# Sheet1.net
KiCad netlist of a schematic drawn in Altium Designer
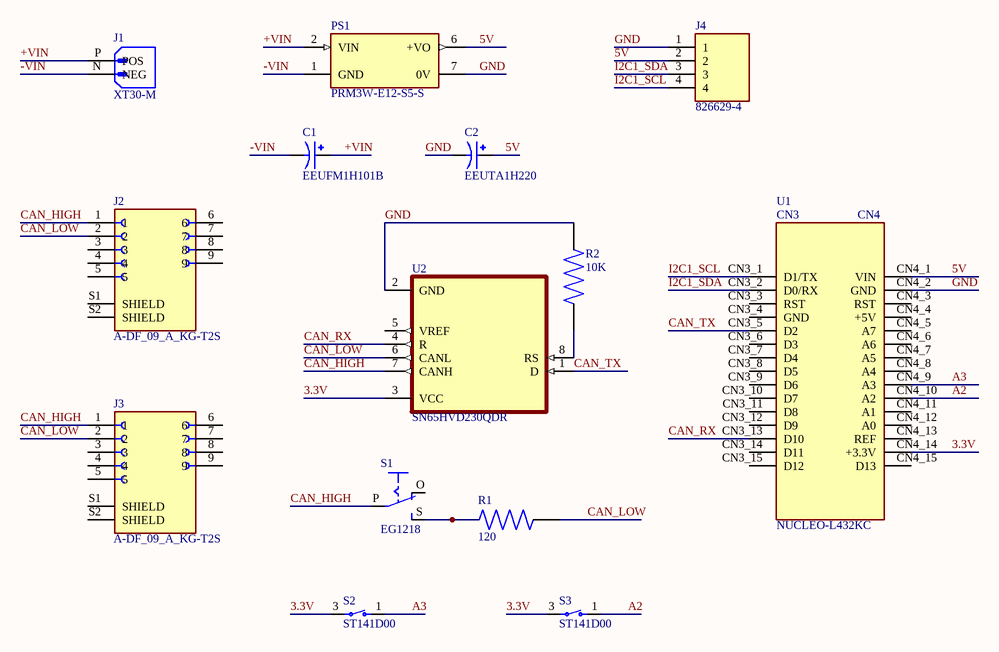
[diagram p0: Sheet1.SchDoc]

(export (version "E")
  (design (tool "Eeschema 10.0.6"))
  (components
    (comp (ref "C1")
      (value "EEUFM1H101B")
      (footprint "CAPPRD500W60D800H1150")
      (description "Cap Aluminum Lytic 100uF 50V 20% (8 X 11.5mm) Radial 5mm 870mA 3000h 105C Ammo Pack")
      (fields (field (name "MF") "Panasonic"))
      (libsource (lib "EEUFM1H101B") (part "EEUFM1H101B"))
    )
    (comp (ref "C2")
      (value "EEUTA1H220")
      (footprint "CAPPRD350W60D800H1150")
      (description "22F 50V Aluminum Electrolytic Capacitors Radial, Can 2000 Hrs @ 125C")
      (fields (field (name "MP") "EEU-TA1H220") (field (name "MF") "Panasonic"))
      (libsource (lib "EEUTA1H220") (part "EEUTA1H220"))
    )
    (comp (ref "J1")
      (value "XT30-M")
      (footprint "AMASS_XT60-M")
      (description "Plug; DC supply; XT60; male; PIN: 2; for cable; soldered; 30A; 500V")
      (fields (field (name "MP") "XT60-M") (field (name "MF") "AMASS"))
      (libsource (lib "XT30-M") (part "XT30-M"))
    )
    (comp (ref "J2")
      (value "A-DF_09_A_KG-T2S")
      (footprint "ASSMANN_A-DF_09_A_KG-T2S")
      (description "9 Position D-Sub Receptacle, Female Sockets Connector")
      (fields (field (name "MF") "Assmann WSW") (field (name "MP") "A-DF 09 A/KG-T2S"))
      (libsource (lib "A-DF_09_A_KG-T2S") (part "A-DF_09_A_KG-T2S"))
    )
    (comp (ref "J3")
      (value "A-DF_09_A_KG-T2S")
      (footprint "ASSMANN_A-DF_09_A_KG-T2S")
      (description "9 Position D-Sub Receptacle, Female Sockets Connector")
      (fields (field (name "MF") "Assmann WSW") (field (name "MP") "A-DF 09 A/KG-T2S"))
      (libsource (lib "A-DF_09_A_KG-T2S") (part "A-DF_09_A_KG-T2S"))
    )
    (comp (ref "J4")
      (value "826629-4")
      (footprint "TE_826629-4")
      (description "Conn Unshrouded Header HDR 4 POS 2.54mm Solder ST Thru-Hole Automotive Carton")
      (fields (field (name "MF") "TE Connectivity"))
      (libsource (lib "826629-4") (part "826629-4"))
    )
    (comp (ref "PS1")
      (value "PRM3W-E12-S5-S")
      (footprint "CONV_PRM3W-E12-S5-S")
      (fields (field (name "MF") "{'manufacturer': u'CUI'}"))
      (libsource (lib "PRM3W-E12-S5-S") (part "PRM3W-E12-S5-S"))
    )
    (comp (ref "R1")
      (value "120")
      (footprint "RESC3216X65N")
      (fields (field (name "MP") "KTR18EZPF9530"))
      (libsource (lib "KTR18EZPF9530") (part "KTR18EZPF9530"))
    )
    (comp (ref "R2")
      (value "10K")
      (footprint "RESC3216X65N")
      (fields (field (name "MP") "KTR18EZPF9530"))
      (libsource (lib "KTR18EZPF9530") (part "KTR18EZPF9530"))
    )
    (comp (ref "S1") (value "EG1218") (footprint "EG1218:EG1218") (libsource (lib "EG1218") (part "EG1218")))
    (comp (ref "S2")
      (value "ST141D00")
      (footprint "SW_ST141D00")
      (description "Toggle Switch SPST Panel Mount")
      (fields (field (name "MF") "E-Switch"))
      (libsource (lib "ST141D00") (part "ST141D00"))
    )
    (comp (ref "S3")
      (value "ST141D00")
      (footprint "SW_ST141D00")
      (description "Toggle Switch SPST Panel Mount")
      (fields (field (name "MF") "E-Switch"))
      (libsource (lib "ST141D00") (part "ST141D00"))
    )
    (comp (ref "U1")
      (value "NUCLEO-L432KC")
      (footprint "MODULE_NUCLEO-L432KC")
      (description "STM32 Nucleo-32 development board with STM32L432KC MCU, supports Arduino connectivity")
      (libsource (lib "NUCLEO-L432KC") (part "NUCLEO-L432KC"))
    )
    (comp (ref "U2")
      (value "SN65HVD230QDR")
      (footprint "SOIC127P599X175-8N")
      (description "3.3-V CAN Transceiver with Standby Mode 8-SOIC -40 to 125")
      (fields (field (name "MF") "Texas Instruments"))
      (libsource (lib "SN65HVD230QDR") (part "SN65HVD230QDR"))
    )
  )
  (nets
    (net (code "1") (name "/+VIN") (class "Default")
      (node (ref "C1") (pin "P") (pinfunction "P_P") (pintype "passive"))
      (node (ref "J1") (pin "P") (pinfunction "POS_P") (pintype "passive"))
      (node (ref "PS1") (pin "2") (pinfunction "VIN_2") (pintype "input"))
    )
    (net (code "2") (name "/-VIN") (class "Default")
      (node (ref "C1") (pin "N") (pinfunction "N_N") (pintype "passive"))
      (node (ref "J1") (pin "N") (pinfunction "NEG_N") (pintype "passive"))
      (node (ref "PS1") (pin "1") (pinfunction "GND_1") (pintype "power_in"))
    )
    (net (code "3") (name "/3.3V") (class "Default")
      (node (ref "S2") (pin "3") (pinfunction "3_3") (pintype "passive"))
      (node (ref "S3") (pin "3") (pinfunction "3_3") (pintype "passive"))
      (node (ref "U1") (pin "CN4_14") (pinfunction "+3.3V_CN4_14") (pintype "power_in"))
      (node (ref "U2") (pin "3") (pinfunction "VCC_3") (pintype "power_in"))
    )
    (net (code "4") (name "/5V") (class "Default")
      (node (ref "C2") (pin "P") (pinfunction "P_P") (pintype "passive"))
      (node (ref "J4") (pin "2") (pinfunction "2_2") (pintype "passive"))
      (node (ref "PS1") (pin "6") (pinfunction "+VO_6") (pintype "output"))
      (node (ref "U1") (pin "CN4_1") (pinfunction "VIN_CN4_1") (pintype "power_in"))
    )
    (net (code "5") (name "/A2") (class "Default")
      (node (ref "S3") (pin "1") (pinfunction "1_1") (pintype "passive"))
      (node (ref "U1") (pin "CN4_10") (pinfunction "A2_CN4_10") (pintype "passive"))
    )
    (net (code "6") (name "/A3") (class "Default")
      (node (ref "S2") (pin "1") (pinfunction "1_1") (pintype "passive"))
      (node (ref "U1") (pin "CN4_9") (pinfunction "A3_CN4_9") (pintype "passive"))
    )
    (net (code "7") (name "/CAN_HIGH") (class "Default")
      (node (ref "J2") (pin "1") (pinfunction "1_1") (pintype "passive"))
      (node (ref "J3") (pin "1") (pinfunction "1_1") (pintype "passive"))
      (node (ref "S1") (pin "P") (pinfunction "P_P") (pintype "passive"))
      (node (ref "U2") (pin "7") (pinfunction "CANH_7") (pintype "output"))
    )
    (net (code "8") (name "/CAN_LOW") (class "Default")
      (node (ref "J2") (pin "2") (pinfunction "2_2") (pintype "passive"))
      (node (ref "J3") (pin "2") (pinfunction "2_2") (pintype "passive"))
      (node (ref "R1") (pin "2") (pinfunction "2_2") (pintype "passive"))
      (node (ref "U2") (pin "6") (pinfunction "CANL_6") (pintype "output"))
    )
    (net (code "9") (name "/CAN_RX") (class "Default")
      (node (ref "U1") (pin "CN3_13") (pinfunction "D10_CN3_13") (pintype "passive"))
      (node (ref "U2") (pin "4") (pinfunction "R_4") (pintype "output"))
    )
    (net (code "10") (name "/CAN_TX") (class "Default")
      (node (ref "U1") (pin "CN3_5") (pinfunction "D2_CN3_5") (pintype "power_in"))
      (node (ref "U2") (pin "1") (pinfunction "D_1") (pintype "input"))
    )
    (net (code "11") (name "/GND") (class "Default")
      (node (ref "C2") (pin "N") (pinfunction "N_N") (pintype "passive"))
      (node (ref "J4") (pin "1") (pinfunction "1_1") (pintype "passive"))
      (node (ref "PS1") (pin "7") (pinfunction "0V_7") (pintype "passive"))
      (node (ref "R2") (pin "2") (pinfunction "2_2") (pintype "passive"))
      (node (ref "U1") (pin "CN4_2") (pinfunction "GND_CN4_2") (pintype "power_in"))
      (node (ref "U2") (pin "2") (pinfunction "GND_2") (pintype "power_in"))
    )
    (net (code "12") (name "/I2C1_SCL") (class "Default")
      (node (ref "J4") (pin "4") (pinfunction "4_4") (pintype "passive"))
      (node (ref "U1") (pin "CN3_1") (pinfunction "D1/TX_CN3_1") (pintype "power_in"))
    )
    (net (code "13") (name "/I2C1_SDA") (class "Default")
      (node (ref "J4") (pin "3") (pinfunction "3_3") (pintype "passive"))
      (node (ref "U1") (pin "CN3_2") (pinfunction "D0/RX_CN3_2") (pintype "power_in"))
    )
    (net (code "14") (name "Net-(R1-Pad1)") (class "Default")
      (node (ref "R1") (pin "1") (pinfunction "1_1") (pintype "passive"))
      (node (ref "S1") (pin "S") (pinfunction "S_S") (pintype "passive"))
    )
    (net (code "15") (name "Net-(U2-RS)") (class "Default")
      (node (ref "R2") (pin "1") (pinfunction "1_1") (pintype "passive"))
      (node (ref "U2") (pin "8") (pinfunction "RS_8") (pintype "input"))
    )
    (net (code "16") (name "unconnected-(J2-Pad3)") (class "Default")
      (node (ref "J2") (pin "3") (pinfunction "3_3") (pintype "passive"))
    )
    (net (code "17") (name "unconnected-(J2-Pad4)") (class "Default")
      (node (ref "J2") (pin "4") (pinfunction "4_4") (pintype "passive"))
    )
    (net (code "18") (name "unconnected-(J2-Pad5)") (class "Default")
      (node (ref "J2") (pin "5") (pinfunction "5_5") (pintype "passive"))
    )
    (net (code "19") (name "unconnected-(J2-Pad6)") (class "Default")
      (node (ref "J2") (pin "6") (pinfunction "6_6") (pintype "passive"))
    )
    (net (code "20") (name "unconnected-(J2-Pad7)") (class "Default")
      (node (ref "J2") (pin "7") (pinfunction "7_7") (pintype "passive"))
    )
    (net (code "21") (name "unconnected-(J2-Pad8)") (class "Default")
      (node (ref "J2") (pin "8") (pinfunction "8_8") (pintype "passive"))
    )
    (net (code "22") (name "unconnected-(J2-Pad9)") (class "Default")
      (node (ref "J2") (pin "9") (pinfunction "9_9") (pintype "passive"))
    )
    (net (code "23") (name "unconnected-(J2-SHIELD-PadS1)") (class "Default")
      (node (ref "J2") (pin "S1") (pinfunction "SHIELD_S1") (pintype "passive"))
    )
    (net (code "24") (name "unconnected-(J2-SHIELD-PadS2)") (class "Default")
      (node (ref "J2") (pin "S2") (pinfunction "SHIELD_S2") (pintype "passive"))
    )
    (net (code "25") (name "unconnected-(J3-Pad3)") (class "Default")
      (node (ref "J3") (pin "3") (pinfunction "3_3") (pintype "passive"))
    )
    (net (code "26") (name "unconnected-(J3-Pad4)") (class "Default")
      (node (ref "J3") (pin "4") (pinfunction "4_4") (pintype "passive"))
    )
    (net (code "27") (name "unconnected-(J3-Pad5)") (class "Default")
      (node (ref "J3") (pin "5") (pinfunction "5_5") (pintype "passive"))
    )
    (net (code "28") (name "unconnected-(J3-Pad6)") (class "Default")
      (node (ref "J3") (pin "6") (pinfunction "6_6") (pintype "passive"))
    )
    (net (code "29") (name "unconnected-(J3-Pad7)") (class "Default")
      (node (ref "J3") (pin "7") (pinfunction "7_7") (pintype "passive"))
    )
    (net (code "30") (name "unconnected-(J3-Pad8)") (class "Default")
      (node (ref "J3") (pin "8") (pinfunction "8_8") (pintype "passive"))
    )
    (net (code "31") (name "unconnected-(J3-Pad9)") (class "Default")
      (node (ref "J3") (pin "9") (pinfunction "9_9") (pintype "passive"))
    )
    (net (code "32") (name "unconnected-(J3-SHIELD-PadS1)") (class "Default")
      (node (ref "J3") (pin "S1") (pinfunction "SHIELD_S1") (pintype "passive"))
    )
    (net (code "33") (name "unconnected-(J3-SHIELD-PadS2)") (class "Default")
      (node (ref "J3") (pin "S2") (pinfunction "SHIELD_S2") (pintype "passive"))
    )
    (net (code "34") (name "unconnected-(S1-PadO)") (class "Default")
      (node (ref "S1") (pin "O") (pinfunction "O_O") (pintype "passive"))
    )
    (net (code "35") (name "unconnected-(U1-+5V-PadCN4_4)") (class "Default")
      (node (ref "U1") (pin "CN4_4") (pinfunction "+5V_CN4_4") (pintype "power_in"))
    )
    (net (code "36") (name "unconnected-(U1-A0-PadCN4_12)") (class "Default")
      (node (ref "U1") (pin "CN4_12") (pinfunction "A0_CN4_12") (pintype "passive"))
    )
    (net (code "37") (name "unconnected-(U1-A1-PadCN4_11)") (class "Default")
      (node (ref "U1") (pin "CN4_11") (pinfunction "A1_CN4_11") (pintype "passive"))
    )
    (net (code "38") (name "unconnected-(U1-A4-PadCN4_8)") (class "Default")
      (node (ref "U1") (pin "CN4_8") (pinfunction "A4_CN4_8") (pintype "passive"))
    )
    (net (code "39") (name "unconnected-(U1-A5-PadCN4_7)") (class "Default")
      (node (ref "U1") (pin "CN4_7") (pinfunction "A5_CN4_7") (pintype "passive"))
    )
    (net (code "40") (name "unconnected-(U1-A6-PadCN4_6)") (class "Default")
      (node (ref "U1") (pin "CN4_6") (pinfunction "A6_CN4_6") (pintype "passive"))
    )
    (net (code "41") (name "unconnected-(U1-A7-PadCN4_5)") (class "Default")
      (node (ref "U1") (pin "CN4_5") (pinfunction "A7_CN4_5") (pintype "passive"))
    )
    (net (code "42") (name "unconnected-(U1-D3-PadCN3_6)") (class "Default")
      (node (ref "U1") (pin "CN3_6") (pinfunction "D3_CN3_6") (pintype "power_in"))
    )
    (net (code "43") (name "unconnected-(U1-D4-PadCN3_7)") (class "Default")
      (node (ref "U1") (pin "CN3_7") (pinfunction "D4_CN3_7") (pintype "power_in"))
    )
    (net (code "44") (name "unconnected-(U1-D5-PadCN3_8)") (class "Default")
      (node (ref "U1") (pin "CN3_8") (pinfunction "D5_CN3_8") (pintype "power_in"))
    )
    (net (code "45") (name "unconnected-(U1-D6-PadCN3_9)") (class "Default")
      (node (ref "U1") (pin "CN3_9") (pinfunction "D6_CN3_9") (pintype "power_in"))
    )
    (net (code "46") (name "unconnected-(U1-D7-PadCN3_10)") (class "Default")
      (node (ref "U1") (pin "CN3_10") (pinfunction "D7_CN3_10") (pintype "power_in"))
    )
    (net (code "47") (name "unconnected-(U1-D8-PadCN3_11)") (class "Default")
      (node (ref "U1") (pin "CN3_11") (pinfunction "D8_CN3_11") (pintype "power_in"))
    )
    (net (code "48") (name "unconnected-(U1-D9-PadCN3_12)") (class "Default")
      (node (ref "U1") (pin "CN3_12") (pinfunction "D9_CN3_12") (pintype "power_in"))
    )
    (net (code "49") (name "unconnected-(U1-D11-PadCN3_14)") (class "Default")
      (node (ref "U1") (pin "CN3_14") (pinfunction "D11_CN3_14") (pintype "power_in"))
    )
    (net (code "50") (name "unconnected-(U1-D12-PadCN3_15)") (class "Default")
      (node (ref "U1") (pin "CN3_15") (pinfunction "D12_CN3_15") (pintype "power_in"))
    )
    (net (code "51") (name "unconnected-(U1-D13-PadCN4_15)") (class "Default")
      (node (ref "U1") (pin "CN4_15") (pinfunction "D13_CN4_15") (pintype "power_in"))
    )
    (net (code "52") (name "unconnected-(U1-GND-PadCN3_4)") (class "Default")
      (node (ref "U1") (pin "CN3_4") (pinfunction "GND_CN3_4") (pintype "power_in"))
    )
    (net (code "53") (name "unconnected-(U1-REF-PadCN4_13)") (class "Default")
      (node (ref "U1") (pin "CN4_13") (pinfunction "REF_CN4_13") (pintype "passive"))
    )
    (net (code "54") (name "unconnected-(U1-RST-PadCN3_3)") (class "Default")
      (node (ref "U1") (pin "CN3_3") (pinfunction "RST_CN3_3") (pintype "power_in"))
    )
    (net (code "55") (name "unconnected-(U1-RST-PadCN4_3)") (class "Default")
      (node (ref "U1") (pin "CN4_3") (pinfunction "RST_CN4_3") (pintype "passive"))
    )
    (net (code "56") (name "unconnected-(U2-VREF-Pad5)") (class "Default")
      (node (ref "U2") (pin "5") (pinfunction "VREF_5") (pintype "output"))
    )
  )
)
